# Sensors.net
KiCad netlist of a schematic drawn in Altium Designer
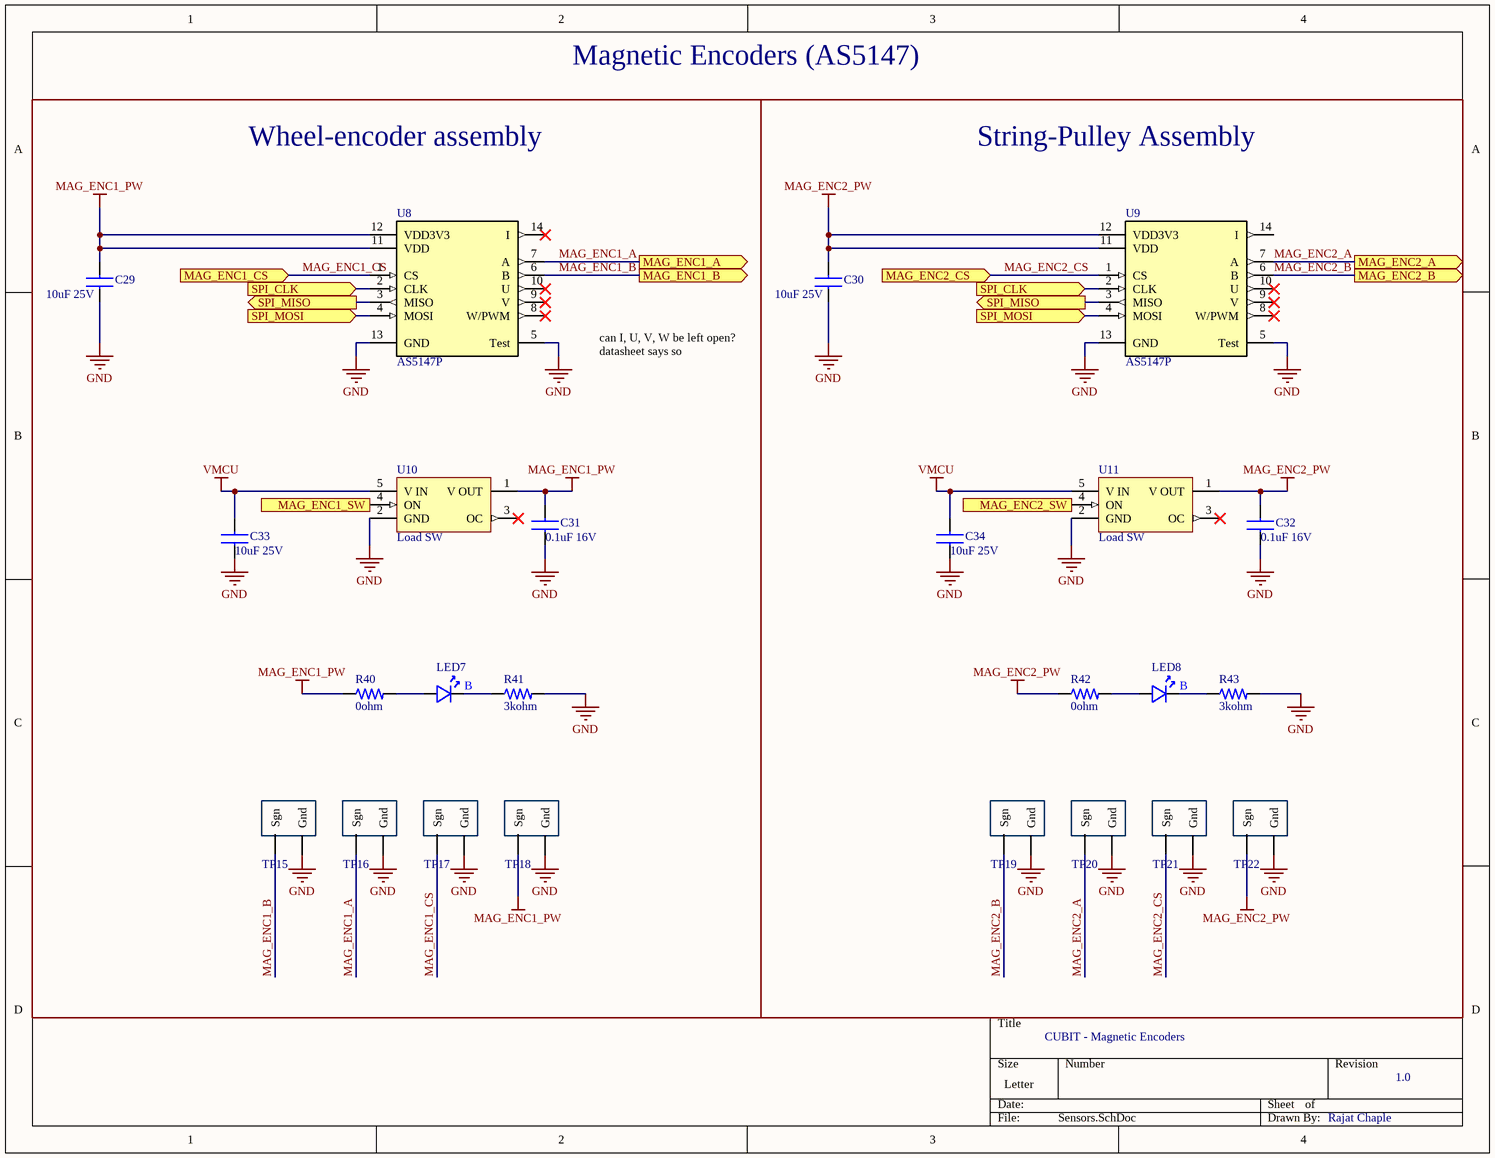
[diagram p0: Sensors.SchDoc]

(export (version "E")
  (design (tool "Eeschema 10.0.6"))
  (components
    (comp (ref "C29")
      (value "10uF 25V")
      (footprint "CAP_0805_02X125")
      (description "Cap 0805 25 V 10 uF ±20% Tolerance X5R Monolithic Ceramic Chip Capacitor")
      (fields
        (field (name "MANUFACTURER") "Murata")
        (field (name "MANUFACTURER PART NUMBER") "GRM21BR61E106KA73K")
      )
      (libsource (lib "LPEDT_proj_lib") (part "GRM21BR61E106KA73K"))
    )
    (comp (ref "C30")
      (value "10uF 25V")
      (footprint "CAP_0805_02X125")
      (description "Cap 0805 25 V 10 uF ±20% Tolerance X5R Monolithic Ceramic Chip Capacitor")
      (fields
        (field (name "MANUFACTURER") "Murata")
        (field (name "MANUFACTURER PART NUMBER") "GRM21BR61E106KA73K")
      )
      (libsource (lib "LPEDT_proj_lib") (part "GRM21BR61E106KA73K"))
    )
    (comp (ref "C31")
      (value "0.1uF 16V")
      (footprint "CAP_0805_02X125")
      (description "Cap Ceramic 0.1uF 16V X7R 10% SMD 0805 125°C Paper T/R")
      (fields
        (field (name "MANUFACTURER") "KEMET")
        (field (name "MANUFACTURER PART NUMBER") "C0805C104K4RACAUTO")
      )
      (libsource (lib "LPEDT_proj_lib") (part "C0805C104K4RACAUTO"))
    )
    (comp (ref "C32")
      (value "0.1uF 16V")
      (footprint "CAP_0805_02X125")
      (description "Cap Ceramic 0.1uF 16V X7R 10% SMD 0805 125°C Paper T/R")
      (fields
        (field (name "MANUFACTURER") "KEMET")
        (field (name "MANUFACTURER PART NUMBER") "C0805C104K4RACAUTO")
      )
      (libsource (lib "LPEDT_proj_lib") (part "C0805C104K4RACAUTO"))
    )
    (comp (ref "C33")
      (value "10uF 25V")
      (footprint "CAP_0805_02X125")
      (description "Cap 0805 25 V 10 uF ±20% Tolerance X5R Monolithic Ceramic Chip Capacitor")
      (fields
        (field (name "MANUFACTURER") "Murata")
        (field (name "MANUFACTURER PART NUMBER") "GRM21BR61E106KA73K")
      )
      (libsource (lib "LPEDT_proj_lib") (part "GRM21BR61E106KA73K"))
    )
    (comp (ref "C34")
      (value "10uF 25V")
      (footprint "CAP_0805_02X125")
      (description "Cap 0805 25 V 10 uF ±20% Tolerance X5R Monolithic Ceramic Chip Capacitor")
      (fields
        (field (name "MANUFACTURER") "Murata")
        (field (name "MANUFACTURER PART NUMBER") "GRM21BR61E106KA73K")
      )
      (libsource (lib "LPEDT_proj_lib") (part "GRM21BR61E106KA73K"))
    )
    (comp (ref "LED7")
      (value "150060BS75000")
      (footprint "LED_0603_RED_WL-SMCW")
      (description "Led, Blue, 470 Nm, 3.2 V, 30 Ma, 145 Mcd Rohs Compliant: Yes")
      (fields (field (name "MANUFACTURER") "Wurth Electronics"))
      (libsource (lib "LPEDT_proj_lib") (part "150060BS75000"))
    )
    (comp (ref "LED8")
      (value "150060BS75000")
      (footprint "LED_0603_RED_WL-SMCW")
      (description "Led, Blue, 470 Nm, 3.2 V, 30 Ma, 145 Mcd Rohs Compliant: Yes")
      (fields (field (name "MANUFACTURER") "Wurth Electronics"))
      (libsource (lib "LPEDT_proj_lib") (part "150060BS75000"))
    )
    (comp (ref "R40")
      (value "0ohm")
      (footprint "CAP_0402_1mm")
      (description "Res 0 Ohms ±5% 0.063 W 0402 Thick Film Surface Mount Chip Resistor")
      (fields
        (field (name "MANUFACTURER") "Samsung")
        (field (name "MANUFACTURER PART NUMBER") "RC1005J000CS")
      )
      (libsource (lib "LPEDT_proj_lib") (part "RC1005J000CS"))
    )
    (comp (ref "R41")
      (value "3kohm")
      (footprint "CAP_0603_1MM")
      (description "Res 3000Ω ± 1.00% 0.1W ± 100ppm/℃ 0603")
      (fields
        (field (name "MANUFACTURER") "Yageo")
        (field (name "MANUFACTURER PART NUMBER") "RC0603FR-073KL")
      )
      (libsource (lib "LPEDT_proj_lib") (part "RC0603FR-073KL"))
    )
    (comp (ref "R42")
      (value "0ohm")
      (footprint "CAP_0402_1mm")
      (description "Res 0 Ohms ±5% 0.063 W 0402 Thick Film Surface Mount Chip Resistor")
      (fields
        (field (name "MANUFACTURER") "Samsung")
        (field (name "MANUFACTURER PART NUMBER") "RC1005J000CS")
      )
      (libsource (lib "LPEDT_proj_lib") (part "RC1005J000CS"))
    )
    (comp (ref "R43")
      (value "3kohm")
      (footprint "CAP_0603_1MM")
      (description "Res 3000Ω ± 1.00% 0.1W ± 100ppm/℃ 0603")
      (fields
        (field (name "MANUFACTURER") "Yageo")
        (field (name "MANUFACTURER PART NUMBER") "RC0603FR-073KL")
      )
      (libsource (lib "LPEDT_proj_lib") (part "RC0603FR-073KL"))
    )
    (comp (ref "TP15")
      (value "10x Probe TP")
      (footprint "TP10x_Probe")
      (description "Test Point 300 mil centers")
      (libsource (lib "LPEDT_proj_lib") (part "TP_10x_Probe"))
    )
    (comp (ref "TP16")
      (value "10x Probe TP")
      (footprint "TP10x_Probe")
      (description "Test Point 300 mil centers")
      (libsource (lib "LPEDT_proj_lib") (part "TP_10x_Probe"))
    )
    (comp (ref "TP17")
      (value "10x Probe TP")
      (footprint "TP10x_Probe")
      (description "Test Point 300 mil centers")
      (libsource (lib "LPEDT_proj_lib") (part "TP_10x_Probe"))
    )
    (comp (ref "TP18")
      (value "10x Probe TP")
      (footprint "TP10x_Probe")
      (description "Test Point 300 mil centers")
      (libsource (lib "LPEDT_proj_lib") (part "TP_10x_Probe"))
    )
    (comp (ref "TP19")
      (value "10x Probe TP")
      (footprint "TP10x_Probe")
      (description "Test Point 300 mil centers")
      (libsource (lib "LPEDT_proj_lib") (part "TP_10x_Probe"))
    )
    (comp (ref "TP20")
      (value "10x Probe TP")
      (footprint "TP10x_Probe")
      (description "Test Point 300 mil centers")
      (libsource (lib "LPEDT_proj_lib") (part "TP_10x_Probe"))
    )
    (comp (ref "TP21")
      (value "10x Probe TP")
      (footprint "TP10x_Probe")
      (description "Test Point 300 mil centers")
      (libsource (lib "LPEDT_proj_lib") (part "TP_10x_Probe"))
    )
    (comp (ref "TP22")
      (value "10x Probe TP")
      (footprint "TP10x_Probe")
      (description "Test Point 300 mil centers")
      (libsource (lib "LPEDT_proj_lib") (part "TP_10x_Probe"))
    )
    (comp (ref "U8")
      (value "AS5147P")
      (footprint "14-TSOP_5x4_4")
      (description "Rotary Position Sensor 5.5V/3.6V Digital Output Automotive 14-Pin TSSOP T/R")
      (fields (field (name "MANUFACTURER") "ams") (field (name "MANUFACTURER PART NUMBER") "AS5147P-HTSM"))
      (libsource (lib "LPEDT_proj_lib") (part "AS5147P-HTSM"))
    )
    (comp (ref "U9")
      (value "AS5147P")
      (footprint "14-TSOP_5x4_4")
      (description "Rotary Position Sensor 5.5V/3.6V Digital Output Automotive 14-Pin TSSOP T/R")
      (fields (field (name "MANUFACTURER") "ams") (field (name "MANUFACTURER PART NUMBER") "AS5147P-HTSM"))
      (libsource (lib "LPEDT_proj_lib") (part "AS5147P-HTSM"))
    )
    (comp (ref "U10")
      (value "Load SW")
      (footprint "SOT65P210X110-5N")
      (description "5.5-V, 0.1-A, 500-mΩ, load switch with current limit and active low enable 5-SC70 -40 to 85")
      (fields
        (field (name "MANUFACTURER") "Texas Instruments")
        (field (name "MANUFACTURER PART NUMBER") "TPS22942DCKR")
      )
      (libsource (lib "LPEDT_proj_lib") (part "TPS22942DCKR"))
    )
    (comp (ref "U11")
      (value "Load SW")
      (footprint "SOT65P210X110-5N")
      (description "5.5-V, 0.1-A, 500-mΩ, load switch with current limit and active low enable 5-SC70 -40 to 85")
      (fields
        (field (name "MANUFACTURER") "Texas Instruments")
        (field (name "MANUFACTURER PART NUMBER") "TPS22942DCKR")
      )
      (libsource (lib "LPEDT_proj_lib") (part "TPS22942DCKR"))
    )
  )
  (nets
    (net (code "1") (name "/MAG_ENC1_A") (class "Default")
      (node (ref "TP16") (pin "1") (pinfunction "Sgn_1") (pintype "passive"))
      (node (ref "U8") (pin "7") (pinfunction "A_7") (pintype "output"))
    )
    (net (code "2") (name "/MAG_ENC1_B") (class "Default")
      (node (ref "TP15") (pin "1") (pinfunction "Sgn_1") (pintype "passive"))
      (node (ref "U8") (pin "6") (pinfunction "B_6") (pintype "output"))
    )
    (net (code "3") (name "/MAG_ENC1_CS") (class "Default")
      (node (ref "TP17") (pin "1") (pinfunction "Sgn_1") (pintype "passive"))
      (node (ref "U8") (pin "1") (pinfunction "CS_1") (pintype "input"))
    )
    (net (code "4") (name "/MAG_ENC1_SW") (class "Default")
      (node (ref "U10") (pin "4") (pinfunction "ON_4") (pintype "input"))
    )
    (net (code "5") (name "/MAG_ENC2_A") (class "Default")
      (node (ref "TP20") (pin "1") (pinfunction "Sgn_1") (pintype "passive"))
      (node (ref "U9") (pin "7") (pinfunction "A_7") (pintype "output"))
    )
    (net (code "6") (name "/MAG_ENC2_B") (class "Default")
      (node (ref "TP19") (pin "1") (pinfunction "Sgn_1") (pintype "passive"))
      (node (ref "U9") (pin "6") (pinfunction "B_6") (pintype "output"))
    )
    (net (code "7") (name "/MAG_ENC2_CS") (class "Default")
      (node (ref "TP21") (pin "1") (pinfunction "Sgn_1") (pintype "passive"))
      (node (ref "U9") (pin "1") (pinfunction "CS_1") (pintype "input"))
    )
    (net (code "8") (name "/MAG_ENC2_SW") (class "Default")
      (node (ref "U11") (pin "4") (pinfunction "ON_4") (pintype "input"))
    )
    (net (code "9") (name "/SPI_CLK") (class "Default")
      (node (ref "U8") (pin "2") (pinfunction "CLK_2") (pintype "input"))
      (node (ref "U9") (pin "2") (pinfunction "CLK_2") (pintype "input"))
    )
    (net (code "10") (name "/SPI_MISO") (class "Default")
      (node (ref "U8") (pin "3") (pinfunction "MISO_3") (pintype "output"))
      (node (ref "U9") (pin "3") (pinfunction "MISO_3") (pintype "output"))
    )
    (net (code "11") (name "/SPI_MOSI") (class "Default")
      (node (ref "U8") (pin "4") (pinfunction "MOSI_4") (pintype "input"))
      (node (ref "U9") (pin "4") (pinfunction "MOSI_4") (pintype "input"))
    )
    (net (code "12") (name "GND") (class "Default")
      (node (ref "C29") (pin "2") (pinfunction "2_2") (pintype "passive"))
      (node (ref "C30") (pin "2") (pinfunction "2_2") (pintype "passive"))
      (node (ref "C31") (pin "2") (pinfunction "2_2") (pintype "passive"))
      (node (ref "C32") (pin "2") (pinfunction "2_2") (pintype "passive"))
      (node (ref "C33") (pin "2") (pinfunction "2_2") (pintype "passive"))
      (node (ref "C34") (pin "2") (pinfunction "2_2") (pintype "passive"))
      (node (ref "R41") (pin "2") (pinfunction "2_2") (pintype "passive"))
      (node (ref "R43") (pin "2") (pinfunction "2_2") (pintype "passive"))
      (node (ref "TP15") (pin "2") (pinfunction "Gnd_2") (pintype "passive"))
      (node (ref "TP16") (pin "2") (pinfunction "Gnd_2") (pintype "passive"))
      (node (ref "TP17") (pin "2") (pinfunction "Gnd_2") (pintype "passive"))
      (node (ref "TP18") (pin "2") (pinfunction "Gnd_2") (pintype "passive"))
      (node (ref "TP19") (pin "2") (pinfunction "Gnd_2") (pintype "passive"))
      (node (ref "TP20") (pin "2") (pinfunction "Gnd_2") (pintype "passive"))
      (node (ref "TP21") (pin "2") (pinfunction "Gnd_2") (pintype "passive"))
      (node (ref "TP22") (pin "2") (pinfunction "Gnd_2") (pintype "passive"))
      (node (ref "U10") (pin "2") (pinfunction "GND_2") (pintype "power_in"))
      (node (ref "U11") (pin "2") (pinfunction "GND_2") (pintype "power_in"))
      (node (ref "U8") (pin "13") (pinfunction "GND_13") (pintype "power_in"))
      (node (ref "U8") (pin "5") (pinfunction "Test_5") (pintype "passive"))
      (node (ref "U9") (pin "13") (pinfunction "GND_13") (pintype "power_in"))
      (node (ref "U9") (pin "5") (pinfunction "Test_5") (pintype "passive"))
    )
    (net (code "13") (name "MAG_ENC1_PW") (class "Default")
      (node (ref "C29") (pin "1") (pinfunction "1_1") (pintype "passive"))
      (node (ref "C31") (pin "1") (pinfunction "1_1") (pintype "passive"))
      (node (ref "R40") (pin "1") (pinfunction "1_1") (pintype "passive"))
      (node (ref "TP18") (pin "1") (pinfunction "Sgn_1") (pintype "passive"))
      (node (ref "U10") (pin "1") (pinfunction "V_OUT_1") (pintype "power_in"))
      (node (ref "U8") (pin "11") (pinfunction "VDD_11") (pintype "power_in"))
      (node (ref "U8") (pin "12") (pinfunction "VDD3V3_12") (pintype "power_in"))
    )
    (net (code "14") (name "MAG_ENC2_PW") (class "Default")
      (node (ref "C30") (pin "1") (pinfunction "1_1") (pintype "passive"))
      (node (ref "C32") (pin "1") (pinfunction "1_1") (pintype "passive"))
      (node (ref "R42") (pin "1") (pinfunction "1_1") (pintype "passive"))
      (node (ref "TP22") (pin "1") (pinfunction "Sgn_1") (pintype "passive"))
      (node (ref "U11") (pin "1") (pinfunction "V_OUT_1") (pintype "power_in"))
      (node (ref "U9") (pin "11") (pinfunction "VDD_11") (pintype "power_in"))
      (node (ref "U9") (pin "12") (pinfunction "VDD3V3_12") (pintype "power_in"))
    )
    (net (code "15") (name "Net-(LED7-PadA)") (class "Default")
      (node (ref "LED7") (pin "A") (pinfunction "A_A") (pintype "passive"))
      (node (ref "R40") (pin "2") (pinfunction "2_2") (pintype "passive"))
    )
    (net (code "16") (name "Net-(LED7-PadC)") (class "Default")
      (node (ref "LED7") (pin "C") (pinfunction "C_C") (pintype "passive"))
      (node (ref "R41") (pin "1") (pinfunction "1_1") (pintype "passive"))
    )
    (net (code "17") (name "Net-(LED8-PadA)") (class "Default")
      (node (ref "LED8") (pin "A") (pinfunction "A_A") (pintype "passive"))
      (node (ref "R42") (pin "2") (pinfunction "2_2") (pintype "passive"))
    )
    (net (code "18") (name "Net-(LED8-PadC)") (class "Default")
      (node (ref "LED8") (pin "C") (pinfunction "C_C") (pintype "passive"))
      (node (ref "R43") (pin "1") (pinfunction "1_1") (pintype "passive"))
    )
    (net (code "19") (name "VMCU") (class "Default")
      (node (ref "C33") (pin "1") (pinfunction "1_1") (pintype "passive"))
      (node (ref "C34") (pin "1") (pinfunction "1_1") (pintype "passive"))
      (node (ref "U10") (pin "5") (pinfunction "V_IN_5") (pintype "power_in"))
      (node (ref "U11") (pin "5") (pinfunction "V_IN_5") (pintype "power_in"))
    )
    (net (code "20") (name "unconnected-(U8-I-Pad14)") (class "Default")
      (node (ref "U8") (pin "14") (pinfunction "I_14") (pintype "output+no_connect"))
    )
    (net (code "21") (name "unconnected-(U8-U-Pad10)") (class "Default")
      (node (ref "U8") (pin "10") (pinfunction "U_10") (pintype "output+no_connect"))
    )
    (net (code "22") (name "unconnected-(U8-V-Pad9)") (class "Default")
      (node (ref "U8") (pin "9") (pinfunction "V_9") (pintype "output+no_connect"))
    )
    (net (code "23") (name "unconnected-(U8-W{slash}PWM-Pad8)") (class "Default")
      (node (ref "U8") (pin "8") (pinfunction "W/PWM_8") (pintype "output+no_connect"))
    )
    (net (code "24") (name "unconnected-(U9-I-Pad14)") (class "Default")
      (node (ref "U9") (pin "14") (pinfunction "I_14") (pintype "output"))
    )
    (net (code "25") (name "unconnected-(U9-U-Pad10)") (class "Default")
      (node (ref "U9") (pin "10") (pinfunction "U_10") (pintype "output+no_connect"))
    )
    (net (code "26") (name "unconnected-(U9-V-Pad9)") (class "Default")
      (node (ref "U9") (pin "9") (pinfunction "V_9") (pintype "output+no_connect"))
    )
    (net (code "27") (name "unconnected-(U9-W{slash}PWM-Pad8)") (class "Default")
      (node (ref "U9") (pin "8") (pinfunction "W/PWM_8") (pintype "output+no_connect"))
    )
    (net (code "28") (name "unconnected-(U10-OC-Pad3)") (class "Default")
      (node (ref "U10") (pin "3") (pinfunction "OC_3") (pintype "output+no_connect"))
    )
    (net (code "29") (name "unconnected-(U11-OC-Pad3)") (class "Default")
      (node (ref "U11") (pin "3") (pinfunction "OC_3") (pintype "output+no_connect"))
    )
  )
)
